# JS7688_convert_board_v1_0.net
KiCad netlist of a schematic drawn in Altium Designer
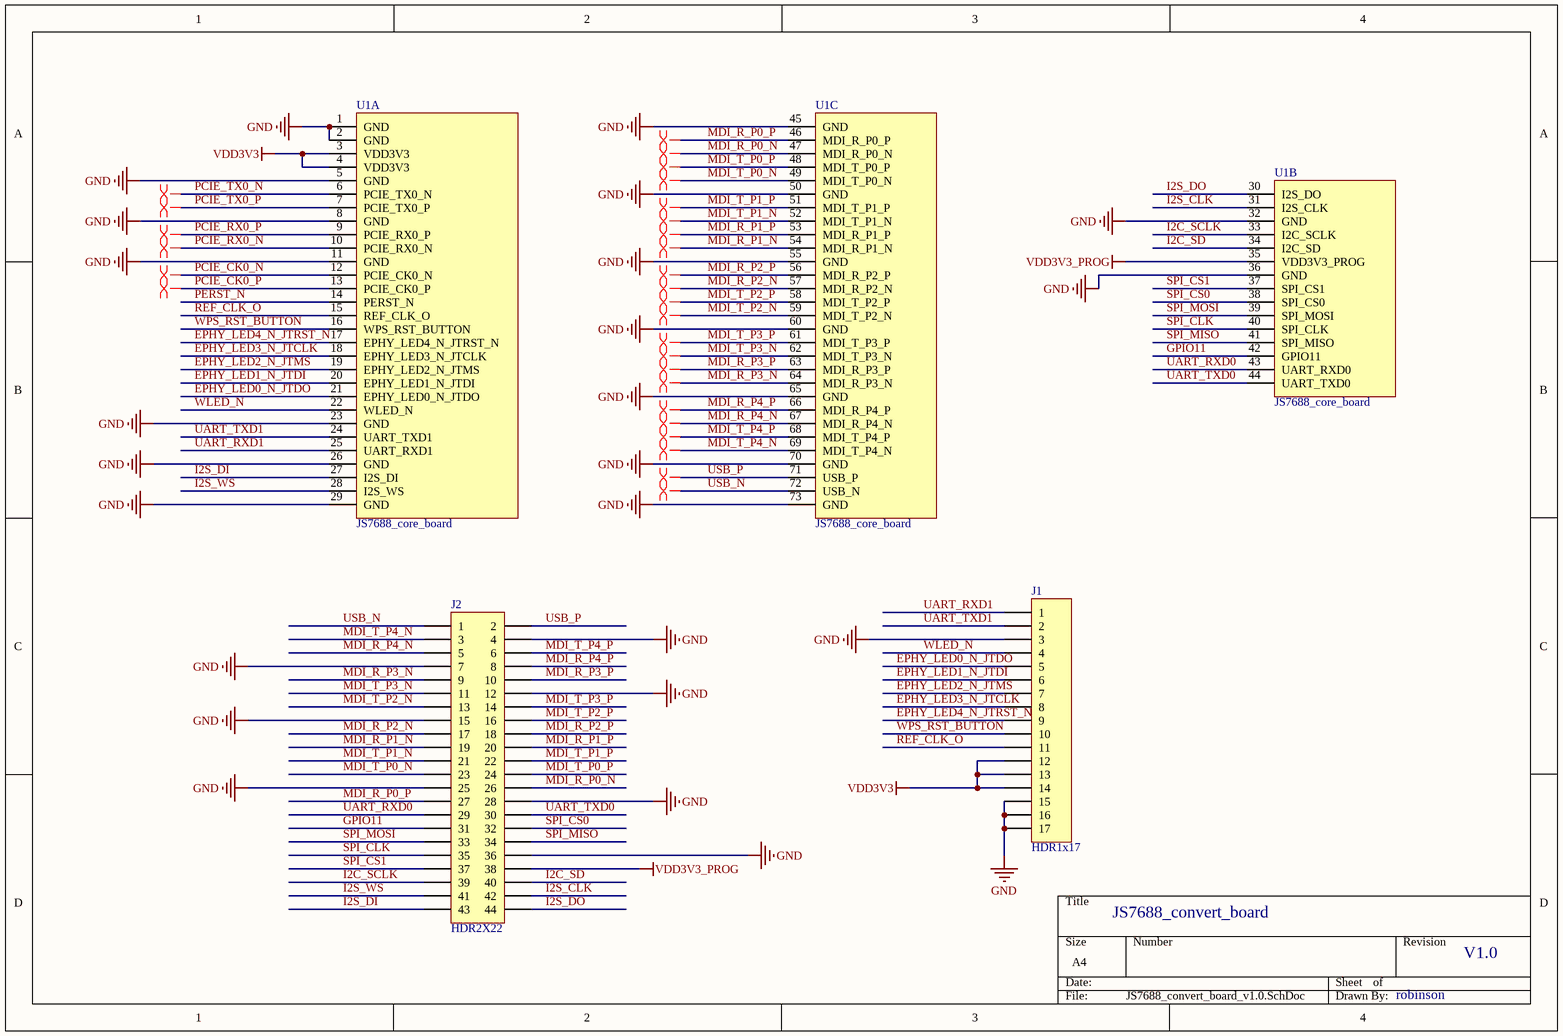
[diagram p0: JS7688_convert_board_v1.0.SchDoc]

(export (version "E")
  (design (tool "Eeschema 10.0.6"))
  (components
    (comp (ref "J1")
      (value "HDR1x17")
      (footprint "MyMiscellaneousConnector:HDR1x17-P-2.0mm")
      (libsource (lib "MyMiscellaneousConnector") (part "HDR1x17"))
    )
    (comp (ref "J2")
      (value "HDR2X22")
      (footprint "MyMiscellaneousConnector:HDR2x22-P-2.0mm")
      (libsource (lib "MyMiscellaneousConnector") (part "HDR2X22"))
    )
    (comp (ref "U1")
      (value "JS7688_core_board")
      (footprint "MyMiscellaneousDevice:JS7688_core_board")
      (libsource (lib "") (part "JS7688_core_board_1"))
    )
  )
  (nets
    (net (code "1") (name "/EPHY_LED0_N_JTDO") (class "Default")
      (node (ref "J1") (pin "5") (pinfunction "5_5") (pintype "passive"))
      (node (ref "U1") (pin "21") (pinfunction "EPHY_LED0_N_JTDO_21") (pintype "passive"))
    )
    (net (code "2") (name "/EPHY_LED1_N_JTDI") (class "Default")
      (node (ref "J1") (pin "6") (pinfunction "6_6") (pintype "passive"))
      (node (ref "U1") (pin "20") (pinfunction "EPHY_LED1_N_JTDI_20") (pintype "passive"))
    )
    (net (code "3") (name "/EPHY_LED2_N_JTMS") (class "Default")
      (node (ref "J1") (pin "7") (pinfunction "7_7") (pintype "passive"))
      (node (ref "U1") (pin "19") (pinfunction "EPHY_LED2_N_JTMS_19") (pintype "passive"))
    )
    (net (code "4") (name "/EPHY_LED3_N_JTCLK") (class "Default")
      (node (ref "J1") (pin "8") (pinfunction "8_8") (pintype "passive"))
      (node (ref "U1") (pin "18") (pinfunction "EPHY_LED3_N_JTCLK_18") (pintype "passive"))
    )
    (net (code "5") (name "/EPHY_LED4_N_JTRST_N") (class "Default")
      (node (ref "J1") (pin "9") (pinfunction "9_9") (pintype "passive"))
      (node (ref "U1") (pin "17") (pinfunction "EPHY_LED4_N_JTRST_N_17") (pintype "passive"))
    )
    (net (code "6") (name "/GPIO11") (class "Default")
      (node (ref "J2") (pin "31") (pinfunction "31_31") (pintype "passive"))
      (node (ref "U1") (pin "42") (pinfunction "GPIO11_42") (pintype "passive"))
    )
    (net (code "7") (name "/I2C_SCLK") (class "Default")
      (node (ref "J2") (pin "39") (pinfunction "39_39") (pintype "passive"))
      (node (ref "U1") (pin "33") (pinfunction "I2C_SCLK_33") (pintype "passive"))
    )
    (net (code "8") (name "/I2C_SD") (class "Default")
      (node (ref "J2") (pin "40") (pinfunction "40_40") (pintype "passive"))
      (node (ref "U1") (pin "34") (pinfunction "I2C_SD_34") (pintype "passive"))
    )
    (net (code "9") (name "/I2S_CLK") (class "Default")
      (node (ref "J2") (pin "42") (pinfunction "42_42") (pintype "passive"))
      (node (ref "U1") (pin "31") (pinfunction "I2S_CLK_31") (pintype "passive"))
    )
    (net (code "10") (name "/I2S_DI") (class "Default")
      (node (ref "J2") (pin "43") (pinfunction "43_43") (pintype "passive"))
      (node (ref "U1") (pin "27") (pinfunction "I2S_DI_27") (pintype "passive"))
    )
    (net (code "11") (name "/I2S_DO") (class "Default")
      (node (ref "J2") (pin "44") (pinfunction "44_44") (pintype "passive"))
      (node (ref "U1") (pin "30") (pinfunction "I2S_DO_30") (pintype "passive"))
    )
    (net (code "12") (name "/I2S_WS") (class "Default")
      (node (ref "J2") (pin "41") (pinfunction "41_41") (pintype "passive"))
      (node (ref "U1") (pin "28") (pinfunction "I2S_WS_28") (pintype "passive"))
    )
    (net (code "13") (name "/MDI_R_P0_N") (class "Default")
      (node (ref "J2") (pin "26") (pinfunction "26_26") (pintype "passive"))
      (node (ref "U1") (pin "47") (pinfunction "MDI_R_P0_N_47") (pintype "passive"))
    )
    (net (code "14") (name "/MDI_R_P0_P") (class "Default")
      (node (ref "J2") (pin "27") (pinfunction "27_27") (pintype "passive"))
      (node (ref "U1") (pin "46") (pinfunction "MDI_R_P0_P_46") (pintype "passive"))
    )
    (net (code "15") (name "/MDI_R_P1_N") (class "Default")
      (node (ref "J2") (pin "19") (pinfunction "19_19") (pintype "passive"))
      (node (ref "U1") (pin "54") (pinfunction "MDI_R_P1_N_54") (pintype "passive"))
    )
    (net (code "16") (name "/MDI_R_P1_P") (class "Default")
      (node (ref "J2") (pin "20") (pinfunction "20_20") (pintype "passive"))
      (node (ref "U1") (pin "53") (pinfunction "MDI_R_P1_P_53") (pintype "passive"))
    )
    (net (code "17") (name "/MDI_R_P2_N") (class "Default")
      (node (ref "J2") (pin "17") (pinfunction "17_17") (pintype "passive"))
      (node (ref "U1") (pin "57") (pinfunction "MDI_R_P2_N_57") (pintype "passive"))
    )
    (net (code "18") (name "/MDI_R_P2_P") (class "Default")
      (node (ref "J2") (pin "18") (pinfunction "18_18") (pintype "passive"))
      (node (ref "U1") (pin "56") (pinfunction "MDI_R_P2_P_56") (pintype "passive"))
    )
    (net (code "19") (name "/MDI_R_P3_N") (class "Default")
      (node (ref "J2") (pin "9") (pinfunction "9_9") (pintype "passive"))
      (node (ref "U1") (pin "64") (pinfunction "MDI_R_P3_N_64") (pintype "passive"))
    )
    (net (code "20") (name "/MDI_R_P3_P") (class "Default")
      (node (ref "J2") (pin "10") (pinfunction "10_10") (pintype "passive"))
      (node (ref "U1") (pin "63") (pinfunction "MDI_R_P3_P_63") (pintype "passive"))
    )
    (net (code "21") (name "/MDI_R_P4_N") (class "Default")
      (node (ref "J2") (pin "5") (pinfunction "5_5") (pintype "passive"))
      (node (ref "U1") (pin "67") (pinfunction "MDI_R_P4_N_67") (pintype "passive"))
    )
    (net (code "22") (name "/MDI_R_P4_P") (class "Default")
      (node (ref "J2") (pin "8") (pinfunction "8_8") (pintype "passive"))
      (node (ref "U1") (pin "66") (pinfunction "MDI_R_P4_P_66") (pintype "passive"))
    )
    (net (code "23") (name "/MDI_T_P0_N") (class "Default")
      (node (ref "J2") (pin "23") (pinfunction "23_23") (pintype "passive"))
      (node (ref "U1") (pin "49") (pinfunction "MDI_T_P0_N_49") (pintype "passive"))
    )
    (net (code "24") (name "/MDI_T_P0_P") (class "Default")
      (node (ref "J2") (pin "24") (pinfunction "24_24") (pintype "passive"))
      (node (ref "U1") (pin "48") (pinfunction "MDI_T_P0_P_48") (pintype "passive"))
    )
    (net (code "25") (name "/MDI_T_P1_N") (class "Default")
      (node (ref "J2") (pin "21") (pinfunction "21_21") (pintype "passive"))
      (node (ref "U1") (pin "52") (pinfunction "MDI_T_P1_N_52") (pintype "passive"))
    )
    (net (code "26") (name "/MDI_T_P1_P") (class "Default")
      (node (ref "J2") (pin "22") (pinfunction "22_22") (pintype "passive"))
      (node (ref "U1") (pin "51") (pinfunction "MDI_T_P1_P_51") (pintype "passive"))
    )
    (net (code "27") (name "/MDI_T_P2_N") (class "Default")
      (node (ref "J2") (pin "13") (pinfunction "13_13") (pintype "passive"))
      (node (ref "U1") (pin "59") (pinfunction "MDI_T_P2_N_59") (pintype "passive"))
    )
    (net (code "28") (name "/MDI_T_P2_P") (class "Default")
      (node (ref "J2") (pin "16") (pinfunction "16_16") (pintype "passive"))
      (node (ref "U1") (pin "58") (pinfunction "MDI_T_P2_P_58") (pintype "passive"))
    )
    (net (code "29") (name "/MDI_T_P3_N") (class "Default")
      (node (ref "J2") (pin "11") (pinfunction "11_11") (pintype "passive"))
      (node (ref "U1") (pin "62") (pinfunction "MDI_T_P3_N_62") (pintype "passive"))
    )
    (net (code "30") (name "/MDI_T_P3_P") (class "Default")
      (node (ref "J2") (pin "14") (pinfunction "14_14") (pintype "passive"))
      (node (ref "U1") (pin "61") (pinfunction "MDI_T_P3_P_61") (pintype "passive"))
    )
    (net (code "31") (name "/MDI_T_P4_N") (class "Default")
      (node (ref "J2") (pin "3") (pinfunction "3_3") (pintype "passive"))
      (node (ref "U1") (pin "69") (pinfunction "MDI_T_P4_N_69") (pintype "passive"))
    )
    (net (code "32") (name "/MDI_T_P4_P") (class "Default")
      (node (ref "J2") (pin "6") (pinfunction "6_6") (pintype "passive"))
      (node (ref "U1") (pin "68") (pinfunction "MDI_T_P4_P_68") (pintype "passive"))
    )
    (net (code "33") (name "/PCIE_CK0_N") (class "Default")
      (node (ref "U1") (pin "12") (pinfunction "PCIE_CK0_N_12") (pintype "passive"))
    )
    (net (code "34") (name "/PCIE_CK0_P") (class "Default")
      (node (ref "U1") (pin "13") (pinfunction "PCIE_CK0_P_13") (pintype "passive"))
    )
    (net (code "35") (name "/PCIE_RX0_N") (class "Default")
      (node (ref "U1") (pin "10") (pinfunction "PCIE_RX0_N_10") (pintype "passive"))
    )
    (net (code "36") (name "/PCIE_RX0_P") (class "Default")
      (node (ref "U1") (pin "9") (pinfunction "PCIE_RX0_P_9") (pintype "passive"))
    )
    (net (code "37") (name "/PCIE_TX0_N") (class "Default")
      (node (ref "U1") (pin "6") (pinfunction "PCIE_TX0_N_6") (pintype "passive"))
    )
    (net (code "38") (name "/PCIE_TX0_P") (class "Default")
      (node (ref "U1") (pin "7") (pinfunction "PCIE_TX0_P_7") (pintype "passive"))
    )
    (net (code "39") (name "/PERST_N") (class "Default")
      (node (ref "U1") (pin "14") (pinfunction "PERST_N_14") (pintype "passive"))
    )
    (net (code "40") (name "/REF_CLK_O") (class "Default")
      (node (ref "J1") (pin "11") (pinfunction "11_11") (pintype "passive"))
      (node (ref "U1") (pin "15") (pinfunction "REF_CLK_O_15") (pintype "passive"))
    )
    (net (code "41") (name "/SPI_CLK") (class "Default")
      (node (ref "J2") (pin "35") (pinfunction "35_35") (pintype "passive"))
      (node (ref "U1") (pin "40") (pinfunction "SPI_CLK_40") (pintype "passive"))
    )
    (net (code "42") (name "/SPI_CS0") (class "Default")
      (node (ref "J2") (pin "32") (pinfunction "32_32") (pintype "passive"))
      (node (ref "U1") (pin "38") (pinfunction "SPI_CS0_38") (pintype "passive"))
    )
    (net (code "43") (name "/SPI_CS1") (class "Default")
      (node (ref "J2") (pin "37") (pinfunction "37_37") (pintype "passive"))
      (node (ref "U1") (pin "37") (pinfunction "SPI_CS1_37") (pintype "passive"))
    )
    (net (code "44") (name "/SPI_MISO") (class "Default")
      (node (ref "J2") (pin "34") (pinfunction "34_34") (pintype "passive"))
      (node (ref "U1") (pin "41") (pinfunction "SPI_MISO_41") (pintype "passive"))
    )
    (net (code "45") (name "/SPI_MOSI") (class "Default")
      (node (ref "J2") (pin "33") (pinfunction "33_33") (pintype "passive"))
      (node (ref "U1") (pin "39") (pinfunction "SPI_MOSI_39") (pintype "passive"))
    )
    (net (code "46") (name "/UART_RXD0") (class "Default")
      (node (ref "J2") (pin "29") (pinfunction "29_29") (pintype "passive"))
      (node (ref "U1") (pin "43") (pinfunction "UART_RXD0_43") (pintype "passive"))
    )
    (net (code "47") (name "/UART_RXD1") (class "Default")
      (node (ref "J1") (pin "1") (pinfunction "1_1") (pintype "passive"))
      (node (ref "U1") (pin "25") (pinfunction "UART_RXD1_25") (pintype "passive"))
    )
    (net (code "48") (name "/UART_TXD0") (class "Default")
      (node (ref "J2") (pin "30") (pinfunction "30_30") (pintype "passive"))
      (node (ref "U1") (pin "44") (pinfunction "UART_TXD0_44") (pintype "passive"))
    )
    (net (code "49") (name "/UART_TXD1") (class "Default")
      (node (ref "J1") (pin "2") (pinfunction "2_2") (pintype "passive"))
      (node (ref "U1") (pin "24") (pinfunction "UART_TXD1_24") (pintype "passive"))
    )
    (net (code "50") (name "/USB_N") (class "Default")
      (node (ref "J2") (pin "1") (pinfunction "1_1") (pintype "passive"))
      (node (ref "U1") (pin "72") (pinfunction "USB_N_72") (pintype "passive"))
    )
    (net (code "51") (name "/USB_P") (class "Default")
      (node (ref "J2") (pin "2") (pinfunction "2_2") (pintype "passive"))
      (node (ref "U1") (pin "71") (pinfunction "USB_P_71") (pintype "passive"))
    )
    (net (code "52") (name "/WLED_N") (class "Default")
      (node (ref "J1") (pin "4") (pinfunction "4_4") (pintype "passive"))
      (node (ref "U1") (pin "22") (pinfunction "WLED_N_22") (pintype "passive"))
    )
    (net (code "53") (name "/WPS_RST_BUTTON") (class "Default")
      (node (ref "J1") (pin "10") (pinfunction "10_10") (pintype "passive"))
      (node (ref "U1") (pin "16") (pinfunction "WPS_RST_BUTTON_16") (pintype "passive"))
    )
    (net (code "54") (name "GND") (class "Default")
      (node (ref "J1") (pin "15") (pinfunction "15_15") (pintype "passive"))
      (node (ref "J1") (pin "16") (pinfunction "16_16") (pintype "passive"))
      (node (ref "J1") (pin "17") (pinfunction "17_17") (pintype "passive"))
      (node (ref "J1") (pin "3") (pinfunction "3_3") (pintype "passive"))
      (node (ref "J2") (pin "12") (pinfunction "12_12") (pintype "passive"))
      (node (ref "J2") (pin "15") (pinfunction "15_15") (pintype "passive"))
      (node (ref "J2") (pin "25") (pinfunction "25_25") (pintype "passive"))
      (node (ref "J2") (pin "28") (pinfunction "28_28") (pintype "passive"))
      (node (ref "J2") (pin "36") (pinfunction "36_36") (pintype "passive"))
      (node (ref "J2") (pin "4") (pinfunction "4_4") (pintype "passive"))
      (node (ref "J2") (pin "7") (pinfunction "7_7") (pintype "passive"))
      (node (ref "U1") (pin "1") (pinfunction "GND_1") (pintype "passive"))
      (node (ref "U1") (pin "11") (pinfunction "GND_11") (pintype "passive"))
      (node (ref "U1") (pin "2") (pinfunction "GND_2") (pintype "passive"))
      (node (ref "U1") (pin "23") (pinfunction "GND_23") (pintype "passive"))
      (node (ref "U1") (pin "26") (pinfunction "GND_26") (pintype "passive"))
      (node (ref "U1") (pin "29") (pinfunction "GND_29") (pintype "passive"))
      (node (ref "U1") (pin "32") (pinfunction "GND_32") (pintype "passive"))
      (node (ref "U1") (pin "36") (pinfunction "GND_36") (pintype "passive"))
      (node (ref "U1") (pin "45") (pinfunction "GND_45") (pintype "passive"))
      (node (ref "U1") (pin "5") (pinfunction "GND_5") (pintype "passive"))
      (node (ref "U1") (pin "50") (pinfunction "GND_50") (pintype "passive"))
      (node (ref "U1") (pin "55") (pinfunction "GND_55") (pintype "passive"))
      (node (ref "U1") (pin "60") (pinfunction "GND_60") (pintype "passive"))
      (node (ref "U1") (pin "65") (pinfunction "GND_65") (pintype "passive"))
      (node (ref "U1") (pin "70") (pinfunction "GND_70") (pintype "passive"))
      (node (ref "U1") (pin "73") (pinfunction "GND_73") (pintype "passive"))
      (node (ref "U1") (pin "8") (pinfunction "GND_8") (pintype "passive"))
    )
    (net (code "55") (name "VDD3V3") (class "Default")
      (node (ref "J1") (pin "12") (pinfunction "12_12") (pintype "passive"))
      (node (ref "J1") (pin "13") (pinfunction "13_13") (pintype "passive"))
      (node (ref "J1") (pin "14") (pinfunction "14_14") (pintype "passive"))
      (node (ref "U1") (pin "3") (pinfunction "VDD3V3_3") (pintype "passive"))
      (node (ref "U1") (pin "4") (pinfunction "VDD3V3_4") (pintype "passive"))
    )
    (net (code "56") (name "VDD3V3_PROG") (class "Default")
      (node (ref "J2") (pin "38") (pinfunction "38_38") (pintype "passive"))
      (node (ref "U1") (pin "35") (pinfunction "VDD3V3_PROG_35") (pintype "passive"))
    )
  )
)
